# stm32f303_devboard.net
KiCad netlist of a schematic drawn in EAGLE
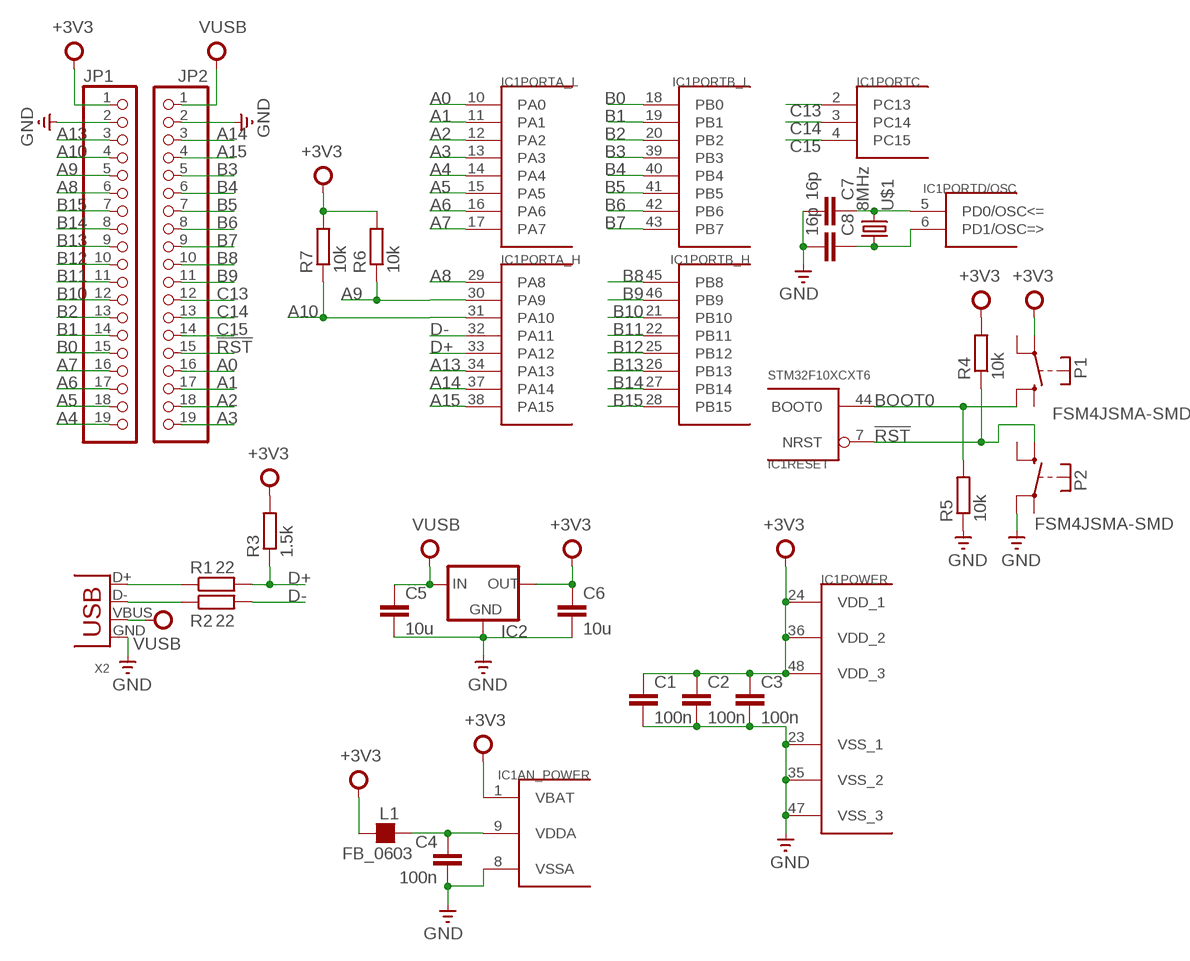
[diagram p0: schematic, sheet 1]

(export (version "E")
  (design (tool "Eeschema 10.0.6"))
  (components
    (comp (ref "C1")
      (value "100n")
      (footprint "eagle-import:C0603")
      (libsource (lib "eagle-import") (part "C-EUC0603"))
    )
    (comp (ref "C2")
      (value "100n")
      (footprint "eagle-import:C0603")
      (libsource (lib "eagle-import") (part "C-EUC0603"))
    )
    (comp (ref "C3")
      (value "100n")
      (footprint "eagle-import:C0603")
      (libsource (lib "eagle-import") (part "C-EUC0603"))
    )
    (comp (ref "C4")
      (value "100n")
      (footprint "eagle-import:C0603")
      (libsource (lib "eagle-import") (part "C-EUC0603"))
    )
    (comp (ref "C5")
      (value "10u")
      (footprint "eagle-import:C0805")
      (libsource (lib "eagle-import") (part "C-EUC0805"))
    )
    (comp (ref "C6")
      (value "10u")
      (footprint "eagle-import:C0805")
      (libsource (lib "eagle-import") (part "C-EUC0805"))
    )
    (comp (ref "C7")
      (value "16p")
      (footprint "eagle-import:C0603")
      (libsource (lib "eagle-import") (part "C-EUC0603"))
    )
    (comp (ref "C8")
      (value "16p")
      (footprint "eagle-import:C0603")
      (libsource (lib "eagle-import") (part "C-EUC0603"))
    )
    (comp (ref "IC1")
      (value "STM32F10XCXT6")
      (footprint "eagle-import:TQFP48")
      (libsource (lib "eagle-import") (part "STM32F10XCXT6"))
    )
    (comp (ref "IC2")
      (value "LM1117")
      (footprint "eagle-import:SOT223")
      (libsource (lib "eagle-import") (part "LM1117"))
    )
    (comp (ref "JP1")
      (value "PINHD-1X19")
      (footprint "eagle-import:1X19")
      (libsource (lib "eagle-import") (part "PINHD-1X19"))
    )
    (comp (ref "JP2")
      (value "PINHD-1X19")
      (footprint "eagle-import:1X19")
      (libsource (lib "eagle-import") (part "PINHD-1X19"))
    )
    (comp (ref "L1")
      (value "FB_0603")
      (footprint "eagle-import:L0603")
      (libsource (lib "eagle-import") (part "FB_0603"))
    )
    (comp (ref "P1")
      (value "FSM4JSMA-SMD")
      (footprint "eagle-import:FSM4JSMA-SMD")
      (libsource (lib "eagle-import") (part "FSM4JSMA-SMD"))
    )
    (comp (ref "P2")
      (value "FSM4JSMA-SMD")
      (footprint "eagle-import:FSM4JSMA-SMD")
      (libsource (lib "eagle-import") (part "FSM4JSMA-SMD"))
    )
    (comp (ref "R1")
      (value "22")
      (footprint "eagle-import:R0603")
      (libsource (lib "eagle-import") (part "R-EU_R0603"))
    )
    (comp (ref "R2")
      (value "22")
      (footprint "eagle-import:R0603")
      (libsource (lib "eagle-import") (part "R-EU_R0603"))
    )
    (comp (ref "R3")
      (value "1.5k")
      (footprint "eagle-import:R0603")
      (libsource (lib "eagle-import") (part "R-EU_R0603"))
    )
    (comp (ref "R4")
      (value "10k")
      (footprint "eagle-import:R0603")
      (libsource (lib "eagle-import") (part "R-EU_R0603"))
    )
    (comp (ref "R5")
      (value "10k")
      (footprint "eagle-import:R0603")
      (libsource (lib "eagle-import") (part "R-EU_R0603"))
    )
    (comp (ref "R6")
      (value "10k")
      (footprint "eagle-import:R0603")
      (libsource (lib "eagle-import") (part "R-EU_R0603"))
    )
    (comp (ref "R7")
      (value "10k")
      (footprint "eagle-import:R0603")
      (libsource (lib "eagle-import") (part "R-EU_R0603"))
    )
    (comp (ref "U$1")
      (value "8MHz")
      (footprint "eagle-import:2-SMD")
      (libsource (lib "eagle-import") (part "7A"))
    )
    (comp (ref "X2")
      (value "USB-MB-S")
      (footprint "eagle-import:USB-MB-S")
      (libsource (lib "eagle-import") (part "USB-MB-S"))
    )
  )
  (nets
    (net (code "1") (name "+3V3") (class "Default")
      (node (ref "C1") (pin "1") (pinfunction "1_1") (pintype "passive"))
      (node (ref "C2") (pin "1") (pinfunction "1_1") (pintype "passive"))
      (node (ref "C3") (pin "1") (pinfunction "1_1") (pintype "passive"))
      (node (ref "C6") (pin "1") (pinfunction "1_1") (pintype "passive"))
      (node (ref "IC1") (pin "1") (pinfunction "VBAT_1") (pintype "power_in"))
      (node (ref "IC1") (pin "24") (pinfunction "VDD_1_24") (pintype "power_in"))
      (node (ref "IC1") (pin "36") (pinfunction "VDD_2_36") (pintype "power_in"))
      (node (ref "IC1") (pin "48") (pinfunction "VDD_3_48") (pintype "power_in"))
      (node (ref "IC2") (pin "2") (pinfunction "OUT_2") (pintype "passive"))
      (node (ref "IC2") (pin "4") (pinfunction "OUT_4") (pintype "passive"))
      (node (ref "JP1") (pin "1") (pinfunction "1_1") (pintype "passive"))
      (node (ref "L1") (pin "2") (pinfunction "2_2") (pintype "passive"))
      (node (ref "P1") (pin "P$1") (pinfunction "P_P$1") (pintype "passive"))
      (node (ref "R3") (pin "2") (pinfunction "2_2") (pintype "passive"))
      (node (ref "R4") (pin "2") (pinfunction "2_2") (pintype "passive"))
      (node (ref "R6") (pin "2") (pinfunction "2_2") (pintype "passive"))
      (node (ref "R7") (pin "2") (pinfunction "2_2") (pintype "passive"))
    )
    (net (code "2") (name "/A0") (class "Default")
      (node (ref "IC1") (pin "10") (pinfunction "PA0_10") (pintype "bidirectional"))
      (node (ref "JP2") (pin "16") (pinfunction "16_16") (pintype "passive"))
    )
    (net (code "3") (name "/A1") (class "Default")
      (node (ref "IC1") (pin "11") (pinfunction "PA1_11") (pintype "bidirectional"))
      (node (ref "JP2") (pin "17") (pinfunction "17_17") (pintype "passive"))
    )
    (net (code "4") (name "/A2") (class "Default")
      (node (ref "IC1") (pin "12") (pinfunction "PA2_12") (pintype "bidirectional"))
      (node (ref "JP2") (pin "18") (pinfunction "18_18") (pintype "passive"))
    )
    (net (code "5") (name "/A3") (class "Default")
      (node (ref "IC1") (pin "13") (pinfunction "PA3_13") (pintype "bidirectional"))
      (node (ref "JP2") (pin "19") (pinfunction "19_19") (pintype "passive"))
    )
    (net (code "6") (name "/A4") (class "Default")
      (node (ref "IC1") (pin "14") (pinfunction "PA4_14") (pintype "bidirectional"))
      (node (ref "JP1") (pin "19") (pinfunction "19_19") (pintype "passive"))
    )
    (net (code "7") (name "/A5") (class "Default")
      (node (ref "IC1") (pin "15") (pinfunction "PA5_15") (pintype "bidirectional"))
      (node (ref "JP1") (pin "18") (pinfunction "18_18") (pintype "passive"))
    )
    (net (code "8") (name "/A6") (class "Default")
      (node (ref "IC1") (pin "16") (pinfunction "PA6_16") (pintype "bidirectional"))
      (node (ref "JP1") (pin "17") (pinfunction "17_17") (pintype "passive"))
    )
    (net (code "9") (name "/A7") (class "Default")
      (node (ref "IC1") (pin "17") (pinfunction "PA7_17") (pintype "bidirectional"))
      (node (ref "JP1") (pin "16") (pinfunction "16_16") (pintype "passive"))
    )
    (net (code "10") (name "/A8") (class "Default")
      (node (ref "IC1") (pin "29") (pinfunction "PA8_29") (pintype "bidirectional"))
      (node (ref "JP1") (pin "6") (pinfunction "6_6") (pintype "passive"))
    )
    (net (code "11") (name "/A9") (class "Default")
      (node (ref "IC1") (pin "30") (pinfunction "PA9_30") (pintype "bidirectional"))
      (node (ref "JP1") (pin "5") (pinfunction "5_5") (pintype "passive"))
      (node (ref "R6") (pin "1") (pinfunction "1_1") (pintype "passive"))
    )
    (net (code "12") (name "/A10") (class "Default")
      (node (ref "IC1") (pin "31") (pinfunction "PA10_31") (pintype "bidirectional"))
      (node (ref "JP1") (pin "4") (pinfunction "4_4") (pintype "passive"))
      (node (ref "R7") (pin "1") (pinfunction "1_1") (pintype "passive"))
    )
    (net (code "13") (name "/A13") (class "Default")
      (node (ref "IC1") (pin "34") (pinfunction "PA13_34") (pintype "bidirectional"))
      (node (ref "JP1") (pin "3") (pinfunction "3_3") (pintype "passive"))
    )
    (net (code "14") (name "/A14") (class "Default")
      (node (ref "IC1") (pin "37") (pinfunction "PA14_37") (pintype "bidirectional"))
      (node (ref "JP2") (pin "3") (pinfunction "3_3") (pintype "passive"))
    )
    (net (code "15") (name "/A15") (class "Default")
      (node (ref "IC1") (pin "38") (pinfunction "PA15_38") (pintype "bidirectional"))
      (node (ref "JP2") (pin "4") (pinfunction "4_4") (pintype "passive"))
    )
    (net (code "16") (name "/B0") (class "Default")
      (node (ref "IC1") (pin "18") (pinfunction "PB0_18") (pintype "bidirectional"))
      (node (ref "JP1") (pin "15") (pinfunction "15_15") (pintype "passive"))
    )
    (net (code "17") (name "/B1") (class "Default")
      (node (ref "IC1") (pin "19") (pinfunction "PB1_19") (pintype "bidirectional"))
      (node (ref "JP1") (pin "14") (pinfunction "14_14") (pintype "passive"))
    )
    (net (code "18") (name "/B2") (class "Default")
      (node (ref "IC1") (pin "20") (pinfunction "PB2_20") (pintype "bidirectional"))
      (node (ref "JP1") (pin "13") (pinfunction "13_13") (pintype "passive"))
    )
    (net (code "19") (name "/B3") (class "Default")
      (node (ref "IC1") (pin "39") (pinfunction "PB3_39") (pintype "bidirectional"))
      (node (ref "JP2") (pin "5") (pinfunction "5_5") (pintype "passive"))
    )
    (net (code "20") (name "/B4") (class "Default")
      (node (ref "IC1") (pin "40") (pinfunction "PB4_40") (pintype "bidirectional"))
      (node (ref "JP2") (pin "6") (pinfunction "6_6") (pintype "passive"))
    )
    (net (code "21") (name "/B5") (class "Default")
      (node (ref "IC1") (pin "41") (pinfunction "PB5_41") (pintype "bidirectional"))
      (node (ref "JP2") (pin "7") (pinfunction "7_7") (pintype "passive"))
    )
    (net (code "22") (name "/B6") (class "Default")
      (node (ref "IC1") (pin "42") (pinfunction "PB6_42") (pintype "bidirectional"))
      (node (ref "JP2") (pin "8") (pinfunction "8_8") (pintype "passive"))
    )
    (net (code "23") (name "/B7") (class "Default")
      (node (ref "IC1") (pin "43") (pinfunction "PB7_43") (pintype "bidirectional"))
      (node (ref "JP2") (pin "9") (pinfunction "9_9") (pintype "passive"))
    )
    (net (code "24") (name "/B8") (class "Default")
      (node (ref "IC1") (pin "45") (pinfunction "PB8_45") (pintype "bidirectional"))
      (node (ref "JP2") (pin "10") (pinfunction "10_10") (pintype "passive"))
    )
    (net (code "25") (name "/B9") (class "Default")
      (node (ref "IC1") (pin "46") (pinfunction "PB9_46") (pintype "bidirectional"))
      (node (ref "JP2") (pin "11") (pinfunction "11_11") (pintype "passive"))
    )
    (net (code "26") (name "/B10") (class "Default")
      (node (ref "IC1") (pin "21") (pinfunction "PB10_21") (pintype "bidirectional"))
      (node (ref "JP1") (pin "12") (pinfunction "12_12") (pintype "passive"))
    )
    (net (code "27") (name "/B11") (class "Default")
      (node (ref "IC1") (pin "22") (pinfunction "PB11_22") (pintype "bidirectional"))
      (node (ref "JP1") (pin "11") (pinfunction "11_11") (pintype "passive"))
    )
    (net (code "28") (name "/B12") (class "Default")
      (node (ref "IC1") (pin "25") (pinfunction "PB12_25") (pintype "bidirectional"))
      (node (ref "JP1") (pin "10") (pinfunction "10_10") (pintype "passive"))
    )
    (net (code "29") (name "/B13") (class "Default")
      (node (ref "IC1") (pin "26") (pinfunction "PB13_26") (pintype "bidirectional"))
      (node (ref "JP1") (pin "9") (pinfunction "9_9") (pintype "passive"))
    )
    (net (code "30") (name "/B14") (class "Default")
      (node (ref "IC1") (pin "27") (pinfunction "PB14_27") (pintype "bidirectional"))
      (node (ref "JP1") (pin "8") (pinfunction "8_8") (pintype "passive"))
    )
    (net (code "31") (name "/B15") (class "Default")
      (node (ref "IC1") (pin "28") (pinfunction "PB15_28") (pintype "bidirectional"))
      (node (ref "JP1") (pin "7") (pinfunction "7_7") (pintype "passive"))
    )
    (net (code "32") (name "/BOOT0") (class "Default")
      (node (ref "IC1") (pin "44") (pinfunction "BOOT0_44") (pintype "input"))
      (node (ref "P1") (pin "P$4") (pinfunction "S_P$4") (pintype "passive"))
      (node (ref "R5") (pin "2") (pinfunction "2_2") (pintype "passive"))
    )
    (net (code "33") (name "/C13") (class "Default")
      (node (ref "IC1") (pin "2") (pinfunction "PC13_2") (pintype "bidirectional"))
      (node (ref "JP2") (pin "12") (pinfunction "12_12") (pintype "passive"))
    )
    (net (code "34") (name "/C14") (class "Default")
      (node (ref "IC1") (pin "3") (pinfunction "PC14_3") (pintype "bidirectional"))
      (node (ref "JP2") (pin "13") (pinfunction "13_13") (pintype "passive"))
    )
    (net (code "35") (name "/C15") (class "Default")
      (node (ref "IC1") (pin "4") (pinfunction "PC15_4") (pintype "bidirectional"))
      (node (ref "JP2") (pin "14") (pinfunction "14_14") (pintype "passive"))
    )
    (net (code "36") (name "/D+") (class "Default")
      (node (ref "IC1") (pin "33") (pinfunction "PA12_33") (pintype "bidirectional"))
      (node (ref "R1") (pin "2") (pinfunction "2_2") (pintype "passive"))
      (node (ref "R3") (pin "1") (pinfunction "1_1") (pintype "passive"))
    )
    (net (code "37") (name "/D-") (class "Default")
      (node (ref "IC1") (pin "32") (pinfunction "PA11_32") (pintype "bidirectional"))
      (node (ref "R2") (pin "2") (pinfunction "2_2") (pintype "passive"))
    )
    (net (code "38") (name "/~{RST}") (class "Default")
      (node (ref "IC1") (pin "7") (pinfunction "NRST_7") (pintype "input"))
      (node (ref "JP2") (pin "15") (pinfunction "15_15") (pintype "passive"))
      (node (ref "P2") (pin "P$3") (pinfunction "S_P$3") (pintype "passive"))
      (node (ref "R4") (pin "1") (pinfunction "1_1") (pintype "passive"))
    )
    (net (code "39") (name "GND") (class "Default")
      (node (ref "C1") (pin "2") (pinfunction "2_2") (pintype "passive"))
      (node (ref "C2") (pin "2") (pinfunction "2_2") (pintype "passive"))
      (node (ref "C3") (pin "2") (pinfunction "2_2") (pintype "passive"))
      (node (ref "C4") (pin "2") (pinfunction "2_2") (pintype "passive"))
      (node (ref "C5") (pin "2") (pinfunction "2_2") (pintype "passive"))
      (node (ref "C6") (pin "2") (pinfunction "2_2") (pintype "passive"))
      (node (ref "C7") (pin "2") (pinfunction "2_2") (pintype "passive"))
      (node (ref "C8") (pin "2") (pinfunction "2_2") (pintype "passive"))
      (node (ref "IC1") (pin "23") (pinfunction "VSS_1_23") (pintype "power_in"))
      (node (ref "IC1") (pin "35") (pinfunction "VSS_2_35") (pintype "power_in"))
      (node (ref "IC1") (pin "47") (pinfunction "VSS_3_47") (pintype "power_in"))
      (node (ref "IC1") (pin "8") (pinfunction "VSSA_8") (pintype "power_in"))
      (node (ref "IC2") (pin "1") (pinfunction "GND_1") (pintype "input"))
      (node (ref "JP1") (pin "2") (pinfunction "2_2") (pintype "passive"))
      (node (ref "JP2") (pin "2") (pinfunction "2_2") (pintype "passive"))
      (node (ref "P2") (pin "P$2") (pinfunction "P_P$2") (pintype "passive"))
      (node (ref "R5") (pin "1") (pinfunction "1_1") (pintype "passive"))
      (node (ref "X2") (pin "GND") (pinfunction "GND_GND") (pintype "bidirectional"))
    )
    (net (code "40") (name "Net-(IC1A-VDDA)") (class "Default")
      (node (ref "C4") (pin "1") (pinfunction "1_1") (pintype "passive"))
      (node (ref "IC1") (pin "9") (pinfunction "VDDA_9") (pintype "power_in"))
      (node (ref "L1") (pin "1") (pinfunction "1_1") (pintype "passive"))
    )
    (net (code "41") (name "Net-(IC1G-PD0{slash}OSC<=)") (class "Default")
      (node (ref "C7") (pin "1") (pinfunction "1_1") (pintype "passive"))
      (node (ref "IC1") (pin "5") (pinfunction "PD0/OSC<=_5") (pintype "bidirectional"))
      (node (ref "U$1") (pin "P$2") (pinfunction "2_P$2") (pintype "passive"))
    )
    (net (code "42") (name "Net-(IC1G-PD1{slash}OSC=>)") (class "Default")
      (node (ref "C8") (pin "1") (pinfunction "1_1") (pintype "passive"))
      (node (ref "IC1") (pin "6") (pinfunction "PD1/OSC=>_6") (pintype "bidirectional"))
      (node (ref "U$1") (pin "P$1") (pinfunction "1_P$1") (pintype "passive"))
    )
    (net (code "43") (name "Net-(R1-Pad1)") (class "Default")
      (node (ref "R1") (pin "1") (pinfunction "1_1") (pintype "passive"))
      (node (ref "X2") (pin "D+") (pinfunction "D+_D+") (pintype "bidirectional"))
    )
    (net (code "44") (name "Net-(R2-Pad1)") (class "Default")
      (node (ref "R2") (pin "1") (pinfunction "1_1") (pintype "passive"))
      (node (ref "X2") (pin "D-") (pinfunction "D-_D-") (pintype "bidirectional"))
    )
    (net (code "45") (name "VUSB") (class "Default")
      (node (ref "C5") (pin "1") (pinfunction "1_1") (pintype "passive"))
      (node (ref "IC2") (pin "3") (pinfunction "IN_3") (pintype "input"))
      (node (ref "JP2") (pin "1") (pinfunction "1_1") (pintype "passive"))
      (node (ref "X2") (pin "VBUS") (pinfunction "VBUS_VBUS") (pintype "bidirectional"))
    )
    (net (code "46") (name "unconnected-(P1-P-PadP$2)") (class "Default")
      (node (ref "P1") (pin "P$2") (pinfunction "P_P$2") (pintype "passive"))
    )
    (net (code "47") (name "unconnected-(P1-S-PadP$3)") (class "Default")
      (node (ref "P1") (pin "P$3") (pinfunction "S_P$3") (pintype "passive"))
    )
    (net (code "48") (name "unconnected-(P2-P-PadP$1)") (class "Default")
      (node (ref "P2") (pin "P$1") (pinfunction "P_P$1") (pintype "passive"))
    )
    (net (code "49") (name "unconnected-(P2-S-PadP$4)") (class "Default")
      (node (ref "P2") (pin "P$4") (pinfunction "S_P$4") (pintype "passive"))
    )
  )
)
